# aaaabbbbbccccc.net
KiCad netlist of a schematic drawn in EAGLE
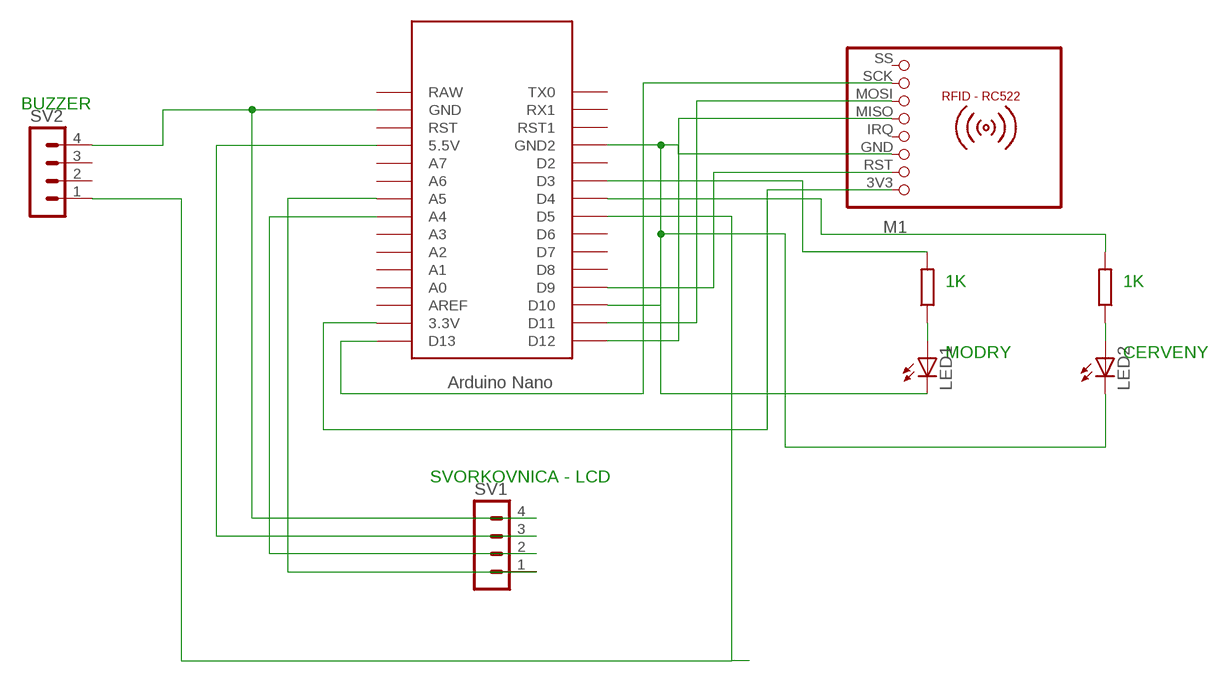
[diagram p0: schematic, sheet 1]

(export (version "E")
  (design (tool "Eeschema 10.0.6"))
  (components
    (comp (ref "LED1")
      (value "LED3MM")
      (footprint "eagle-import:LED3MM")
      (libsource (lib "eagle-import") (part "LED3MM"))
    )
    (comp (ref "LED2")
      (value "LED3MM")
      (footprint "eagle-import:LED3MM")
      (libsource (lib "eagle-import") (part "LED3MM"))
    )
    (comp (ref "M1")
      (value "RFID-RC522")
      (footprint "eagle-import:RFID-RC522")
      (libsource (lib "eagle-import") (part "RFID-RC522"))
    )
    (comp (ref "SV1")
      (value "MA04-1")
      (footprint "eagle-import:MA04-1")
      (libsource (lib "eagle-import") (part "MA04-1"))
    )
    (comp (ref "SV2")
      (value "MA04-1")
      (footprint "eagle-import:MA04-1")
      (libsource (lib "eagle-import") (part "MA04-1"))
    )
    (comp (ref "U$1")
      (value "NANO")
      (footprint "eagle-import:NANO")
      (libsource (lib "eagle-import") (part "NANO"))
    )
  )
  (nets
    (net (code "1") (name "Net-(LED1-C)") (class "Default")
      (node (ref "LED1") (pin "K") (pinfunction "C_K") (pintype "passive"))
      (node (ref "LED2") (pin "K") (pinfunction "C_K") (pintype "passive"))
      (node (ref "M1") (pin "GND") (pinfunction "3_GND") (pintype "passive"))
      (node (ref "U$1") (pin "GND1") (pinfunction "GND2_GND1") (pintype "bidirectional"))
    )
    (net (code "2") (name "Net-(M1-1)") (class "Default")
      (node (ref "M1") (pin "3V3") (pinfunction "1_3V3") (pintype "passive"))
      (node (ref "U$1") (pin "3.3V") (pinfunction "3.3V_3.3V") (pintype "bidirectional"))
    )
    (net (code "3") (name "Net-(M1-2)") (class "Default")
      (node (ref "M1") (pin "RST") (pinfunction "2_RST") (pintype "passive"))
      (node (ref "U$1") (pin "D9") (pinfunction "D9_D9") (pintype "bidirectional"))
    )
    (net (code "4") (name "Net-(M1-5)") (class "Default")
      (node (ref "M1") (pin "MISO") (pinfunction "5_MISO") (pintype "passive"))
      (node (ref "U$1") (pin "D12") (pinfunction "D12_D12") (pintype "bidirectional"))
    )
    (net (code "5") (name "Net-(M1-6)") (class "Default")
      (node (ref "M1") (pin "MOSI") (pinfunction "6_MOSI") (pintype "passive"))
      (node (ref "U$1") (pin "D11") (pinfunction "D11_D11") (pintype "bidirectional"))
    )
    (net (code "6") (name "Net-(M1-7)") (class "Default")
      (node (ref "M1") (pin "SCK") (pinfunction "7_SCK") (pintype "passive"))
      (node (ref "U$1") (pin "D13") (pinfunction "D13_D13") (pintype "bidirectional"))
    )
    (net (code "7") (name "Net-(SV1-Pad1)") (class "Default")
      (node (ref "SV1") (pin "1") (pinfunction "1_1") (pintype "passive"))
      (node (ref "U$1") (pin "A5") (pinfunction "A5_A5") (pintype "bidirectional"))
    )
    (net (code "8") (name "Net-(SV1-Pad2)") (class "Default")
      (node (ref "SV1") (pin "2") (pinfunction "2_2") (pintype "passive"))
      (node (ref "U$1") (pin "A4") (pinfunction "A4_A4") (pintype "bidirectional"))
    )
    (net (code "9") (name "Net-(SV1-Pad4)") (class "Default")
      (node (ref "SV1") (pin "4") (pinfunction "4_4") (pintype "passive"))
      (node (ref "SV2") (pin "4") (pinfunction "4_4") (pintype "passive"))
      (node (ref "U$1") (pin "GND") (pinfunction "GND_GND") (pintype "bidirectional"))
    )
    (net (code "10") (name "Net-(SV2-Pad1)") (class "Default")
      (node (ref "SV2") (pin "1") (pinfunction "1_1") (pintype "passive"))
      (node (ref "U$1") (pin "D5") (pinfunction "D5_D5") (pintype "bidirectional"))
    )
    (net (code "11") (name "Net-(U$1-5.5V)") (class "Default")
      (node (ref "SV1") (pin "3") (pinfunction "3_3") (pintype "passive"))
      (node (ref "U$1") (pin "5V") (pinfunction "5.5V_5V") (pintype "bidirectional"))
    )
    (net (code "12") (name "unconnected-(LED1-PadA)") (class "Default")
      (node (ref "LED1") (pin "A") (pinfunction "A_A") (pintype "passive"))
    )
    (net (code "13") (name "unconnected-(LED2-PadA)") (class "Default")
      (node (ref "LED2") (pin "A") (pinfunction "A_A") (pintype "passive"))
    )
    (net (code "14") (name "unconnected-(M1-4-PadIRQ)") (class "Default")
      (node (ref "M1") (pin "IRQ") (pinfunction "4_IRQ") (pintype "passive"))
    )
    (net (code "15") (name "unconnected-(M1-8-PadSS)") (class "Default")
      (node (ref "M1") (pin "SS") (pinfunction "8_SS") (pintype "passive"))
    )
    (net (code "16") (name "unconnected-(SV2-Pad2)") (class "Default")
      (node (ref "SV2") (pin "2") (pinfunction "2_2") (pintype "passive"))
    )
    (net (code "17") (name "unconnected-(SV2-Pad3)") (class "Default")
      (node (ref "SV2") (pin "3") (pinfunction "3_3") (pintype "passive"))
    )
    (net (code "18") (name "unconnected-(U$1-PadA0)") (class "Default")
      (node (ref "U$1") (pin "A0") (pinfunction "A0_A0") (pintype "bidirectional"))
    )
    (net (code "19") (name "unconnected-(U$1-PadA1)") (class "Default")
      (node (ref "U$1") (pin "A1") (pinfunction "A1_A1") (pintype "bidirectional"))
    )
    (net (code "20") (name "unconnected-(U$1-PadA2)") (class "Default")
      (node (ref "U$1") (pin "A2") (pinfunction "A2_A2") (pintype "bidirectional"))
    )
    (net (code "21") (name "unconnected-(U$1-PadA3)") (class "Default")
      (node (ref "U$1") (pin "A3") (pinfunction "A3_A3") (pintype "bidirectional"))
    )
    (net (code "22") (name "unconnected-(U$1-PadA6)") (class "Default")
      (node (ref "U$1") (pin "A6") (pinfunction "A6_A6") (pintype "bidirectional"))
    )
    (net (code "23") (name "unconnected-(U$1-PadA7)") (class "Default")
      (node (ref "U$1") (pin "A7") (pinfunction "A7_A7") (pintype "bidirectional"))
    )
    (net (code "24") (name "unconnected-(U$1-PadAREF)") (class "Default")
      (node (ref "U$1") (pin "AREF") (pinfunction "AREF_AREF") (pintype "bidirectional"))
    )
    (net (code "25") (name "unconnected-(U$1-PadD2)") (class "Default")
      (node (ref "U$1") (pin "D2") (pinfunction "D2_D2") (pintype "bidirectional"))
    )
    (net (code "26") (name "unconnected-(U$1-PadD3)") (class "Default")
      (node (ref "U$1") (pin "D3") (pinfunction "D3_D3") (pintype "bidirectional"))
    )
    (net (code "27") (name "unconnected-(U$1-PadD4)") (class "Default")
      (node (ref "U$1") (pin "D4") (pinfunction "D4_D4") (pintype "bidirectional"))
    )
    (net (code "28") (name "unconnected-(U$1-PadD6)") (class "Default")
      (node (ref "U$1") (pin "D6") (pinfunction "D6_D6") (pintype "bidirectional"))
    )
    (net (code "29") (name "unconnected-(U$1-PadD7)") (class "Default")
      (node (ref "U$1") (pin "D7") (pinfunction "D7_D7") (pintype "bidirectional"))
    )
    (net (code "30") (name "unconnected-(U$1-PadD8)") (class "Default")
      (node (ref "U$1") (pin "D8") (pinfunction "D8_D8") (pintype "bidirectional"))
    )
    (net (code "31") (name "unconnected-(U$1-PadD10)") (class "Default")
      (node (ref "U$1") (pin "D10") (pinfunction "D10_D10") (pintype "bidirectional"))
    )
    (net (code "32") (name "unconnected-(U$1-PadICSP1)") (class "Default")
      (node (ref "U$1") (pin "ICSP1") (pinfunction "ICSP1_ICSP1") (pintype "bidirectional"))
    )
    (net (code "33") (name "unconnected-(U$1-PadICSP2)") (class "Default")
      (node (ref "U$1") (pin "ICSP2") (pinfunction "ICSP2_ICSP2") (pintype "bidirectional"))
    )
    (net (code "34") (name "unconnected-(U$1-PadICSP3)") (class "Default")
      (node (ref "U$1") (pin "ICSP3") (pinfunction "ICSP3_ICSP3") (pintype "bidirectional"))
    )
    (net (code "35") (name "unconnected-(U$1-PadICSP4)") (class "Default")
      (node (ref "U$1") (pin "ICSP4") (pinfunction "ICSP4_ICSP4") (pintype "bidirectional"))
    )
    (net (code "36") (name "unconnected-(U$1-PadICSP5)") (class "Default")
      (node (ref "U$1") (pin "ICSP5") (pinfunction "ICSP5_ICSP5") (pintype "bidirectional"))
    )
    (net (code "37") (name "unconnected-(U$1-PadICSP6)") (class "Default")
      (node (ref "U$1") (pin "ICSP6") (pinfunction "ICSP6_ICSP6") (pintype "bidirectional"))
    )
    (net (code "38") (name "unconnected-(U$1-PadRAW)") (class "Default")
      (node (ref "U$1") (pin "RAW") (pinfunction "RAW_RAW") (pintype "bidirectional"))
    )
    (net (code "39") (name "unconnected-(U$1-PadRST)") (class "Default")
      (node (ref "U$1") (pin "RST") (pinfunction "RST_RST") (pintype "bidirectional"))
    )
    (net (code "40") (name "unconnected-(U$1-PadRST1)") (class "Default")
      (node (ref "U$1") (pin "RST1") (pinfunction "RST1_RST1") (pintype "bidirectional"))
    )
    (net (code "41") (name "unconnected-(U$1-PadRX1)") (class "Default")
      (node (ref "U$1") (pin "RX1") (pinfunction "RX1_RX1") (pintype "bidirectional"))
    )
    (net (code "42") (name "unconnected-(U$1-PadTX0)") (class "Default")
      (node (ref "U$1") (pin "TX0") (pinfunction "TX0_TX0") (pintype "bidirectional"))
    )
  )
)
